# Blinky_Jaras.net
KiCad netlist of a schematic drawn in EAGLE
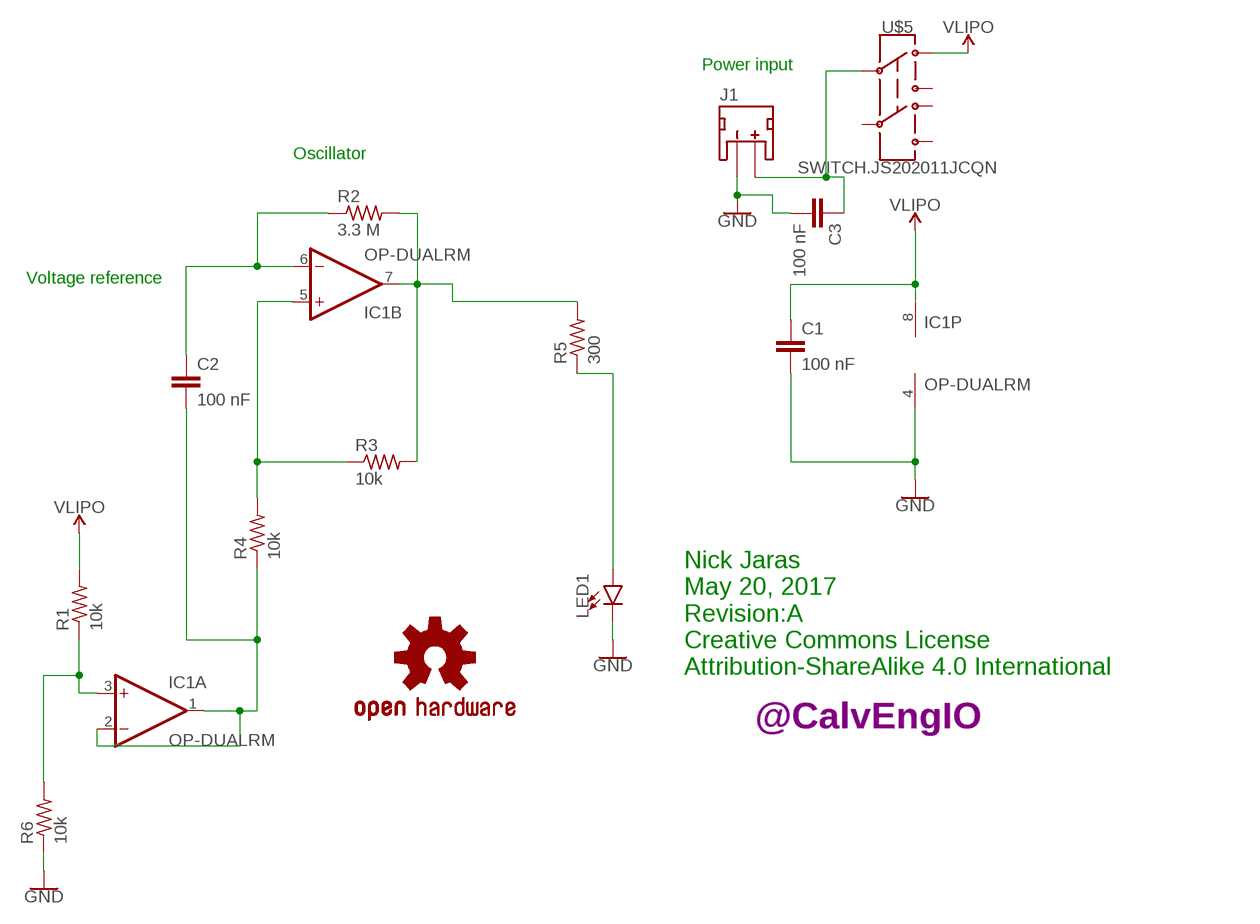
[diagram p0: schematic, sheet 1]

(export (version "E")
  (design (tool "Eeschema 10.0.6"))
  (components
    (comp (ref "C1")
      (value "100 nF")
      (footprint "eagle-import:C0402")
      (libsource (lib "eagle-import") (part "CAPACITOR0402"))
    )
    (comp (ref "C2")
      (value "100 nF")
      (footprint "eagle-import:C0402")
      (libsource (lib "eagle-import") (part "CAPACITOR0402"))
    )
    (comp (ref "C3")
      (value "100 nF")
      (footprint "eagle-import:C0402")
      (libsource (lib "eagle-import") (part "CAPACITOR0402"))
    )
    (comp (ref "IC1")
      (value "OP-DUALRM")
      (footprint "eagle-import:MSOP08")
      (fields (field (name "MF") "ALTERA CORPORATION") (field (name "MPN") "AD8607ARMZ-REEL"))
      (libsource (lib "eagle-import") (part "OP-DUALRM"))
    )
    (comp (ref "J1")
      (value "JST_2MM_MALE")
      (footprint "eagle-import:JST-2-SMD")
      (libsource (lib "eagle-import") (part "JST_2MM_MALE"))
    )
    (comp (ref "LED1")
      (value "LED0603")
      (footprint "eagle-import:LED-0603")
      (libsource (lib "eagle-import") (part "LED0603"))
    )
    (comp (ref "LOGO1")
      (value "OSHW-LOGOS")
      (footprint "eagle-import:OSHW-LOGO-S")
      (libsource (lib "eagle-import") (part "OSHW-LOGOS"))
    )
    (comp (ref "R1")
      (value "10k")
      (footprint "eagle-import:R0402")
      (libsource (lib "eagle-import") (part "RESISTOR0402"))
    )
    (comp (ref "R2")
      (value "3.3 M")
      (footprint "eagle-import:R0402")
      (libsource (lib "eagle-import") (part "RESISTOR0402"))
    )
    (comp (ref "R3")
      (value "10k")
      (footprint "eagle-import:R0402")
      (libsource (lib "eagle-import") (part "RESISTOR0402"))
    )
    (comp (ref "R4")
      (value "10k")
      (footprint "eagle-import:R0402")
      (libsource (lib "eagle-import") (part "RESISTOR0402"))
    )
    (comp (ref "R5")
      (value "300")
      (footprint "eagle-import:R0402")
      (libsource (lib "eagle-import") (part "RESISTOR0402"))
    )
    (comp (ref "R6")
      (value "10k")
      (footprint "eagle-import:R0402")
      (libsource (lib "eagle-import") (part "RESISTOR0402"))
    )
    (comp (ref "U$4")
      (value "CALVENGIO_HANDLEHANDLE.05")
      (footprint "eagle-import:CALVENGIO_HANDLE.05")
      (libsource (lib "eagle-import") (part "CALVENGIO_HANDLEHANDLE.05"))
    )
    (comp (ref "U$5")
      (value "SWITCH.JS202011JCQN")
      (footprint "eagle-import:SWITCH.00")
      (libsource (lib "eagle-import") (part "SWITCH.JS202011JCQN"))
    )
  )
  (nets
    (net (code "1") (name "GND") (class "Default")
      (node (ref "C1") (pin "2") (pinfunction "2_2") (pintype "passive"))
      (node (ref "C3") (pin "2") (pinfunction "2_2") (pintype "passive"))
      (node (ref "IC1") (pin "4") (pinfunction "V-_4") (pintype "power_in"))
      (node (ref "J1") (pin "1") (pinfunction "-_1") (pintype "bidirectional"))
      (node (ref "LED1") (pin "C") (pinfunction "C_C") (pintype "passive"))
      (node (ref "R6") (pin "1") (pinfunction "1_1") (pintype "passive"))
    )
    (net (code "2") (name "Net-(IC1A-+IN)") (class "Default")
      (node (ref "IC1") (pin "3") (pinfunction "+IN_3") (pintype "input"))
      (node (ref "R1") (pin "1") (pinfunction "1_1") (pintype "passive"))
      (node (ref "R6") (pin "2") (pinfunction "2_2") (pintype "passive"))
    )
    (net (code "3") (name "Net-(IC1A--IN)") (class "Default")
      (node (ref "C2") (pin "2") (pinfunction "2_2") (pintype "passive"))
      (node (ref "IC1") (pin "1") (pinfunction "OUT_1") (pintype "output"))
      (node (ref "IC1") (pin "2") (pinfunction "-IN_2") (pintype "input"))
      (node (ref "R4") (pin "1") (pinfunction "1_1") (pintype "passive"))
    )
    (net (code "4") (name "Net-(IC1B-+IN)") (class "Default")
      (node (ref "IC1") (pin "5") (pinfunction "+IN_5") (pintype "input"))
      (node (ref "R3") (pin "1") (pinfunction "1_1") (pintype "passive"))
      (node (ref "R4") (pin "2") (pinfunction "2_2") (pintype "passive"))
    )
    (net (code "5") (name "Net-(IC1B--IN)") (class "Default")
      (node (ref "C2") (pin "1") (pinfunction "1_1") (pintype "passive"))
      (node (ref "IC1") (pin "6") (pinfunction "-IN_6") (pintype "input"))
      (node (ref "R2") (pin "1") (pinfunction "1_1") (pintype "passive"))
    )
    (net (code "6") (name "Net-(IC1B-OUT)") (class "Default")
      (node (ref "IC1") (pin "7") (pinfunction "OUT_7") (pintype "output"))
      (node (ref "R2") (pin "2") (pinfunction "2_2") (pintype "passive"))
      (node (ref "R3") (pin "2") (pinfunction "2_2") (pintype "passive"))
      (node (ref "R5") (pin "2") (pinfunction "2_2") (pintype "passive"))
    )
    (net (code "7") (name "Net-(J1-+)") (class "Default")
      (node (ref "C3") (pin "1") (pinfunction "1_1") (pintype "passive"))
      (node (ref "J1") (pin "2") (pinfunction "+_2") (pintype "bidirectional"))
      (node (ref "U$5") (pin "2") (pinfunction "2_2") (pintype "bidirectional"))
    )
    (net (code "8") (name "Net-(LED1-PadA)") (class "Default")
      (node (ref "LED1") (pin "A") (pinfunction "A_A") (pintype "passive"))
      (node (ref "R5") (pin "1") (pinfunction "1_1") (pintype "passive"))
    )
    (net (code "9") (name "VLIPO") (class "Default")
      (node (ref "C1") (pin "1") (pinfunction "1_1") (pintype "passive"))
      (node (ref "IC1") (pin "8") (pinfunction "V+_8") (pintype "power_in"))
      (node (ref "R1") (pin "2") (pinfunction "2_2") (pintype "passive"))
      (node (ref "U$5") (pin "1") (pinfunction "1_1") (pintype "bidirectional"))
    )
    (net (code "10") (name "unconnected-(J1-PAD1-PadNC1)") (class "Default")
      (node (ref "J1") (pin "NC1") (pinfunction "PAD1_NC1") (pintype "bidirectional"))
    )
    (net (code "11") (name "unconnected-(J1-PAD2-PadNC2)") (class "Default")
      (node (ref "J1") (pin "NC2") (pinfunction "PAD2_NC2") (pintype "bidirectional"))
    )
    (net (code "12") (name "unconnected-(U$5-Pad3)") (class "Default")
      (node (ref "U$5") (pin "3") (pinfunction "3_3") (pintype "bidirectional"))
    )
    (net (code "13") (name "unconnected-(U$5-Pad5)") (class "Default")
      (node (ref "U$5") (pin "5") (pinfunction "5_5") (pintype "bidirectional"))
    )
    (net (code "14") (name "unconnected-(U$5-Pad6)") (class "Default")
      (node (ref "U$5") (pin "6") (pinfunction "6_6") (pintype "bidirectional"))
    )
    (net (code "15") (name "unconnected-(U$5-Pad7)") (class "Default")
      (node (ref "U$5") (pin "7") (pinfunction "7_7") (pintype "bidirectional"))
    )
  )
)
